# Grove-Base-for-ESPr-Developer.net
KiCad netlist of a schematic drawn in EAGLE
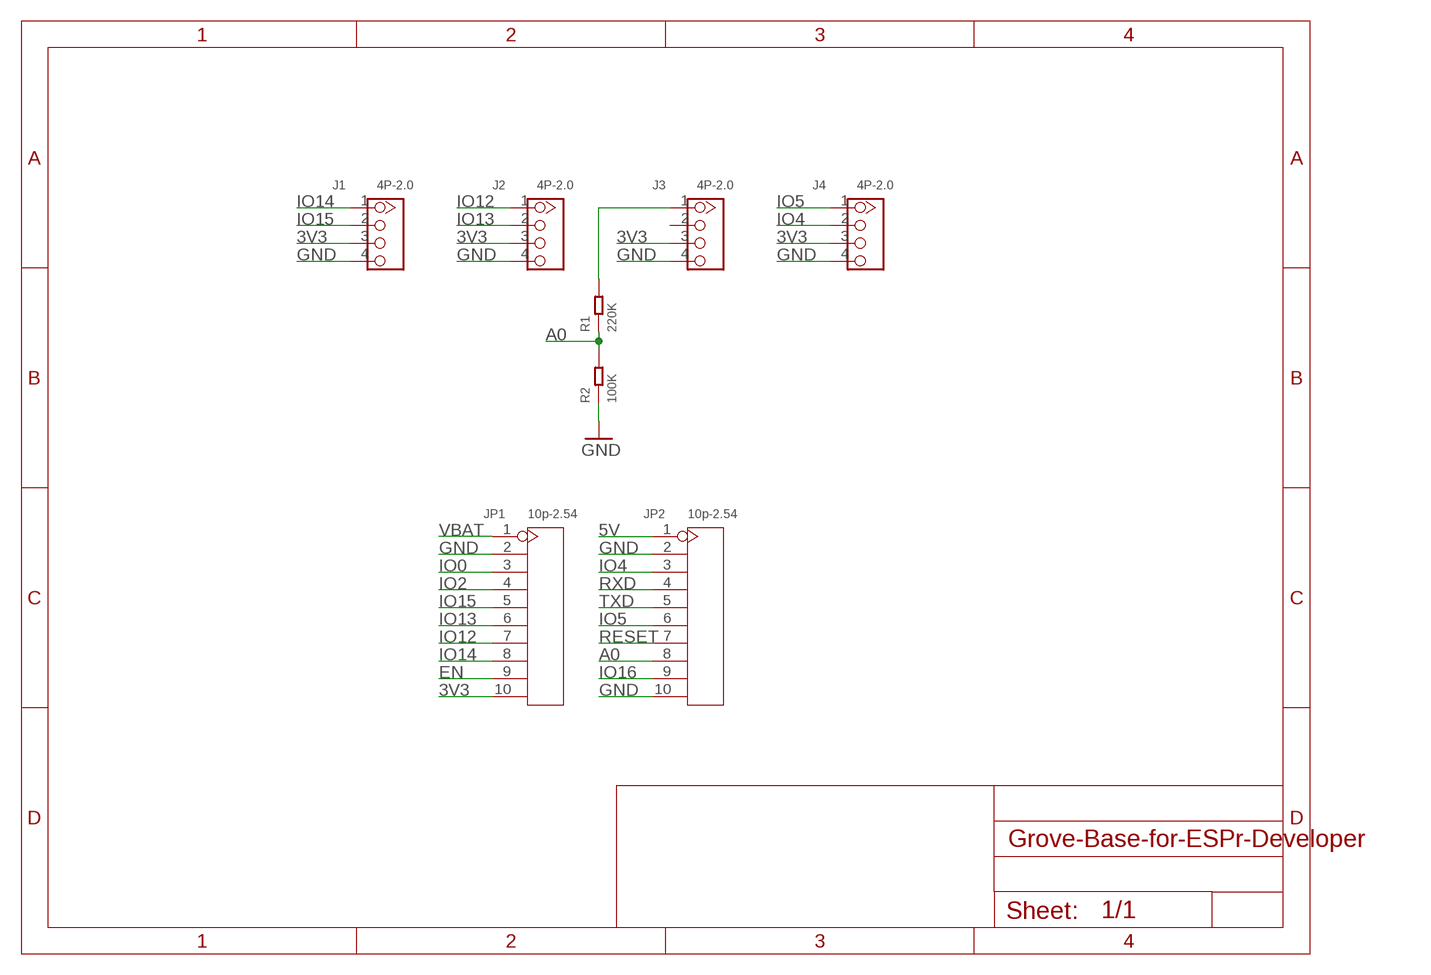
[diagram p0: schematic, sheet 1]

(export (version "E")
  (design (tool "Eeschema 10.0.6"))
  (components
    (comp (ref "J1")
      (value "4P-2.0")
      (footprint "eagle-import:HW4-2.0")
      (libsource (lib "eagle-import") (part "GROVE-CONNECTOR-DIP(4P-2.0)"))
    )
    (comp (ref "J2")
      (value "4P-2.0")
      (footprint "eagle-import:HW4-2.0")
      (libsource (lib "eagle-import") (part "GROVE-CONNECTOR-DIP(4P-2.0)"))
    )
    (comp (ref "J3")
      (value "4P-2.0")
      (footprint "eagle-import:HW4-2.0")
      (libsource (lib "eagle-import") (part "GROVE-CONNECTOR-DIP(4P-2.0)"))
    )
    (comp (ref "J4")
      (value "4P-2.0")
      (footprint "eagle-import:HW4-2.0")
      (libsource (lib "eagle-import") (part "GROVE-CONNECTOR-DIP(4P-2.0)"))
    )
    (comp (ref "JP1")
      (value "10p-2.54")
      (footprint "eagle-import:H10-2.54")
      (fields (field (name "MPN") "P125-1110A0BS116AX"))
      (libsource (lib "eagle-import") (part "DIP-BLACK-MALE-HEADER-VERT(10P-2.54)"))
    )
    (comp (ref "JP2")
      (value "10p-2.54")
      (footprint "eagle-import:H10-2.54")
      (fields (field (name "MPN") "P125-1110A0BS116AX"))
      (libsource (lib "eagle-import") (part "DIP-BLACK-MALE-HEADER-VERT(10P-2.54)"))
    )
    (comp (ref "R1")
      (value "220K")
      (footprint "eagle-import:R0603")
      (fields (field (name "MPN") "RC0603FR-07220KL"))
      (libsource (lib "eagle-import") (part "SMD-RES-220K-1%-1/10W(0603)"))
    )
    (comp (ref "R2")
      (value "100K")
      (footprint "eagle-import:R0603")
      (fields (field (name "MPN") "RC0603FR-07100KL"))
      (libsource (lib "eagle-import") (part "SMD-RES-100K-1%-1/10W(0603)"))
    )
  )
  (nets
    (net (code "1") (name "/3V3") (class "Default")
      (node (ref "J1") (pin "3") (pinfunction "3_3") (pintype "bidirectional"))
      (node (ref "J2") (pin "3") (pinfunction "3_3") (pintype "bidirectional"))
      (node (ref "J3") (pin "3") (pinfunction "3_3") (pintype "bidirectional"))
      (node (ref "J4") (pin "3") (pinfunction "3_3") (pintype "bidirectional"))
      (node (ref "JP1") (pin "10") (pinfunction "10_10") (pintype "bidirectional"))
    )
    (net (code "2") (name "/5V") (class "Default")
      (node (ref "JP2") (pin "1") (pinfunction "1_1") (pintype "bidirectional"))
    )
    (net (code "3") (name "/A0") (class "Default")
      (node (ref "JP2") (pin "8") (pinfunction "8_8") (pintype "bidirectional"))
      (node (ref "R1") (pin "1") (pinfunction "1_1") (pintype "passive"))
      (node (ref "R2") (pin "2") (pinfunction "2_2") (pintype "passive"))
    )
    (net (code "4") (name "/EN") (class "Default")
      (node (ref "JP1") (pin "9") (pinfunction "9_9") (pintype "bidirectional"))
    )
    (net (code "5") (name "/IO0") (class "Default")
      (node (ref "JP1") (pin "3") (pinfunction "3_3") (pintype "bidirectional"))
    )
    (net (code "6") (name "/IO2") (class "Default")
      (node (ref "JP1") (pin "4") (pinfunction "4_4") (pintype "bidirectional"))
    )
    (net (code "7") (name "/IO4") (class "Default")
      (node (ref "J4") (pin "2") (pinfunction "2_2") (pintype "bidirectional"))
      (node (ref "JP2") (pin "3") (pinfunction "3_3") (pintype "bidirectional"))
    )
    (net (code "8") (name "/IO5") (class "Default")
      (node (ref "J4") (pin "1") (pinfunction "1_1") (pintype "bidirectional"))
      (node (ref "JP2") (pin "6") (pinfunction "6_6") (pintype "bidirectional"))
    )
    (net (code "9") (name "/IO12") (class "Default")
      (node (ref "J2") (pin "1") (pinfunction "1_1") (pintype "bidirectional"))
      (node (ref "JP1") (pin "7") (pinfunction "7_7") (pintype "bidirectional"))
    )
    (net (code "10") (name "/IO13") (class "Default")
      (node (ref "J2") (pin "2") (pinfunction "2_2") (pintype "bidirectional"))
      (node (ref "JP1") (pin "6") (pinfunction "6_6") (pintype "bidirectional"))
    )
    (net (code "11") (name "/IO14") (class "Default")
      (node (ref "J1") (pin "1") (pinfunction "1_1") (pintype "bidirectional"))
      (node (ref "JP1") (pin "8") (pinfunction "8_8") (pintype "bidirectional"))
    )
    (net (code "12") (name "/IO15") (class "Default")
      (node (ref "J1") (pin "2") (pinfunction "2_2") (pintype "bidirectional"))
      (node (ref "JP1") (pin "5") (pinfunction "5_5") (pintype "bidirectional"))
    )
    (net (code "13") (name "/IO16") (class "Default")
      (node (ref "JP2") (pin "9") (pinfunction "9_9") (pintype "bidirectional"))
    )
    (net (code "14") (name "/RESET") (class "Default")
      (node (ref "JP2") (pin "7") (pinfunction "7_7") (pintype "bidirectional"))
    )
    (net (code "15") (name "/RXD") (class "Default")
      (node (ref "JP2") (pin "4") (pinfunction "4_4") (pintype "bidirectional"))
    )
    (net (code "16") (name "/TXD") (class "Default")
      (node (ref "JP2") (pin "5") (pinfunction "5_5") (pintype "bidirectional"))
    )
    (net (code "17") (name "/VBAT") (class "Default")
      (node (ref "JP1") (pin "1") (pinfunction "1_1") (pintype "bidirectional"))
    )
    (net (code "18") (name "GND") (class "Default")
      (node (ref "J1") (pin "4") (pinfunction "4_4") (pintype "bidirectional"))
      (node (ref "J2") (pin "4") (pinfunction "4_4") (pintype "bidirectional"))
      (node (ref "J3") (pin "4") (pinfunction "4_4") (pintype "bidirectional"))
      (node (ref "J4") (pin "4") (pinfunction "4_4") (pintype "bidirectional"))
      (node (ref "JP1") (pin "2") (pinfunction "2_2") (pintype "bidirectional"))
      (node (ref "JP2") (pin "10") (pinfunction "10_10") (pintype "bidirectional"))
      (node (ref "JP2") (pin "2") (pinfunction "2_2") (pintype "bidirectional"))
      (node (ref "R2") (pin "1") (pinfunction "1_1") (pintype "passive"))
    )
    (net (code "19") (name "Net-(J3-Pad1)") (class "Default")
      (node (ref "J3") (pin "1") (pinfunction "1_1") (pintype "bidirectional"))
      (node (ref "R1") (pin "2") (pinfunction "2_2") (pintype "passive"))
    )
    (net (code "20") (name "unconnected-(J3-Pad2)") (class "Default")
      (node (ref "J3") (pin "2") (pinfunction "2_2") (pintype "bidirectional"))
    )
  )
)
